# 13-Fusing.net
KiCad netlist of a schematic drawn in Altium Designer
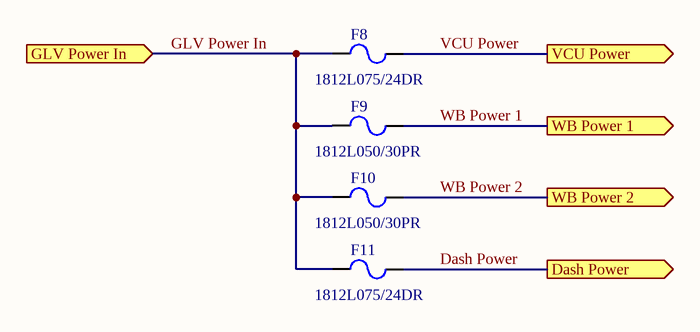
[diagram p0: 13-Fusing.SchDoc]

(export (version "E")
  (design (tool "Eeschema 10.0.6"))
  (components
    (comp (ref "F8")
      (value "1812L075/24DR")
      (footprint "LFUS-1812L07524DR_V")
      (description "Poly-Fuse(R) Resettable PTC, 24 V, 100 A, -40 to 85 degC, 2-Pin SMD, RoHS, Tape and Reel")
      (fields (field (name "MANUFACTURER") "Littelfuse"))
      (libsource (lib "Altium Content Vault") (part "FUSE-2"))
    )
    (comp (ref "F9")
      (value "1812L050/30PR")
      (footprint "LFUS-1812L05030PR_V")
      (description "PTC Resettable Fuse, 0.8 W, 30 V, -40 to 85 degC, 2-Pin SMD, RoHS, Tape and Reel")
      (fields (field (name "MANUFACTURER") "Littelfuse-Inc."))
      (libsource (lib "Altium Content Vault") (part "FUSE-2"))
    )
    (comp (ref "F10")
      (value "1812L050/30PR")
      (footprint "LFUS-1812L05030PR_V")
      (description "PTC Resettable Fuse, 0.8 W, 30 V, -40 to 85 degC, 2-Pin SMD, RoHS, Tape and Reel")
      (fields (field (name "MANUFACTURER") "Littelfuse-Inc."))
      (libsource (lib "Altium Content Vault") (part "FUSE-2"))
    )
    (comp (ref "F11")
      (value "1812L075/24DR")
      (footprint "LFUS-1812L07524DR_V")
      (description "Poly-Fuse(R) Resettable PTC, 24 V, 100 A, -40 to 85 degC, 2-Pin SMD, RoHS, Tape and Reel")
      (fields (field (name "MANUFACTURER") "Littelfuse"))
      (libsource (lib "Altium Content Vault") (part "FUSE-2"))
    )
  )
  (nets
    (net (code "1") (name "/Dash Power") (class "Default")
      (node (ref "F11") (pin "2") (pinfunction "2_2") (pintype "passive"))
    )
    (net (code "2") (name "/GLV Power In") (class "Default")
      (node (ref "F10") (pin "1") (pinfunction "1_1") (pintype "passive"))
      (node (ref "F11") (pin "1") (pinfunction "1_1") (pintype "passive"))
      (node (ref "F8") (pin "1") (pinfunction "1_1") (pintype "passive"))
      (node (ref "F9") (pin "1") (pinfunction "1_1") (pintype "passive"))
    )
    (net (code "3") (name "/VCU Power") (class "Default")
      (node (ref "F8") (pin "2") (pinfunction "2_2") (pintype "passive"))
    )
    (net (code "4") (name "/WB Power 1") (class "Default")
      (node (ref "F9") (pin "2") (pinfunction "2_2") (pintype "passive"))
    )
    (net (code "5") (name "/WB Power 2") (class "Default")
      (node (ref "F10") (pin "2") (pinfunction "2_2") (pintype "passive"))
    )
  )
)
